# MIXR_UI.net
KiCad netlist of a schematic drawn in Altium Designer
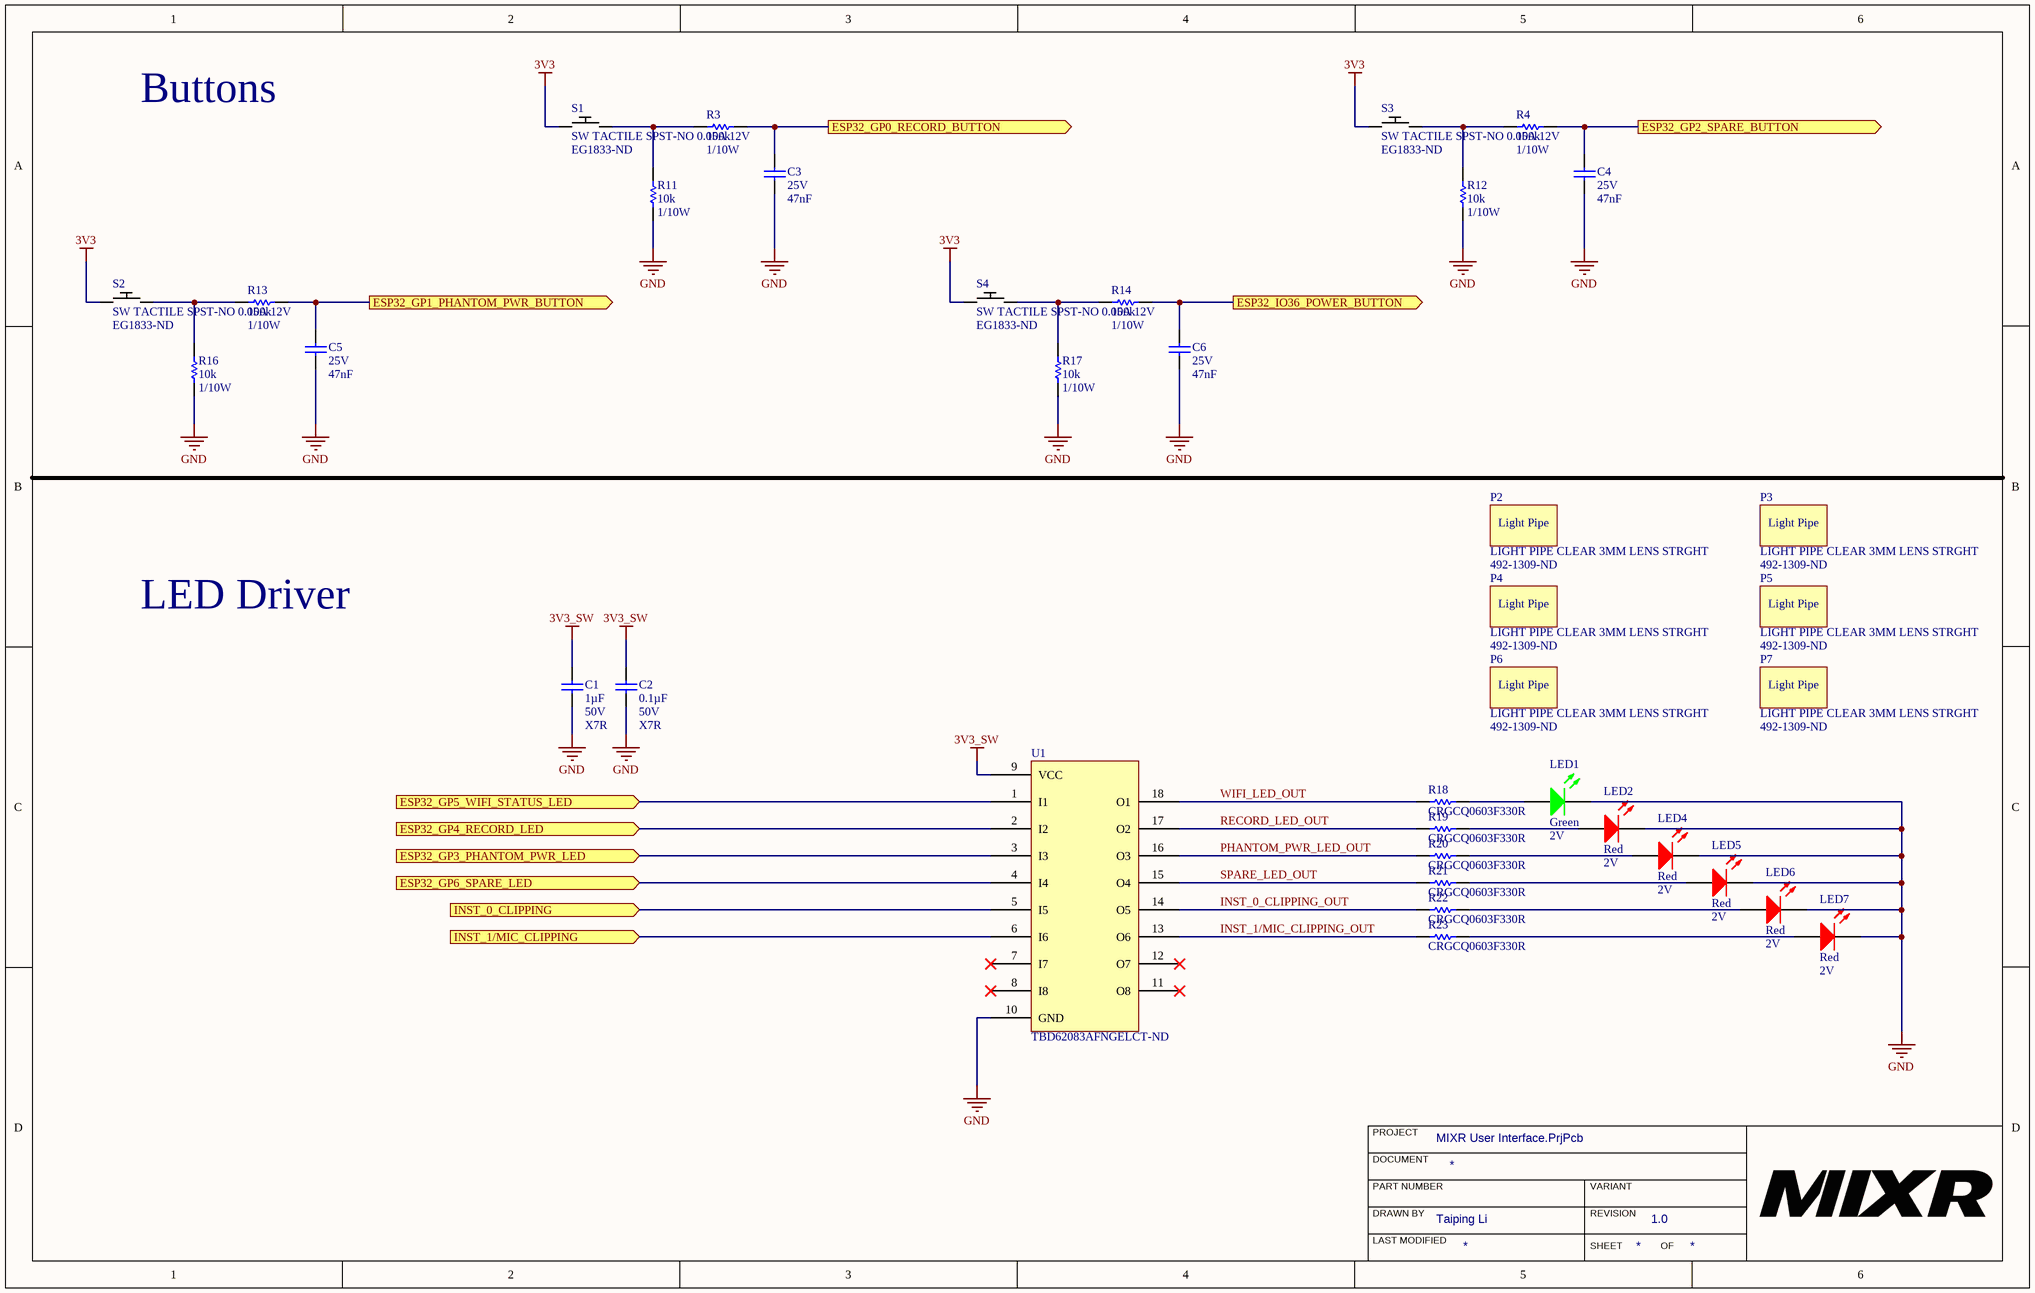
[diagram p0: MIXR UI.SchDoc]

(export (version "E")
  (design (tool "Eeschema 10.0.6"))
  (components
    (comp (ref "C1")
      (value "CAP CER 1UF 50V 10% X7R 0603")
      (footprint "CAP, 0603")
      (description "1µF ±10% 50V Ceramic Capacitor X7R 0603 (1608 Metric)")
      (fields
        (field (name "TOLERANCE") "±10%")
        (field (name "CAPACITANCE") "1µF")
        (field (name "VOLTAGE") "50V")
        (field (name "TEMPERATURE COEFFICIENT") "X7R")
      )
      (libsource (lib "Schematic Diagrams") (part "CAP CER 1UF 50V 10% X7R 0603"))
    )
    (comp (ref "C2")
      (value "CAP CER 0.1UF 50V 10% X7R 0603")
      (footprint "CAP, 0603")
      (description "0.10µF ±10% 50V Ceramic Capacitor X7R 0603 (1608 Metric)")
      (fields
        (field (name "TOLERANCE") "±10%")
        (field (name "CAPACITANCE") "0.1µF")
        (field (name "VOLTAGE") "50V")
        (field (name "TEMPERATURE COEFFICIENT") "X7R")
      )
      (libsource (lib "Schematic Diagrams") (part "CAP CER 0.1UF 50V 10% X7R 0603"))
    )
    (comp (ref "C3")
      (value "CAP CER 0.047UF 10% 25V X7R 0603")
      (footprint "CAP, 0603")
      (description "0.047µF ±10% 25V Ceramic Capacitor X7R 0603 (1608 Metric)")
      (fields
        (field (name "MANUFACTURER") "KEMET")
        (field (name "TOLERANCE") "10%")
        (field (name "VOLTAGE") "25V")
        (field (name "CAPACITANCE") "47nF")
      )
      (libsource (lib "Schematic Diagrams") (part "CAP CER 0.047UF 10% 25V X7R 0603"))
    )
    (comp (ref "C4")
      (value "CAP CER 0.047UF 10% 25V X7R 0603")
      (footprint "CAP, 0603")
      (description "0.047µF ±10% 25V Ceramic Capacitor X7R 0603 (1608 Metric)")
      (fields
        (field (name "MANUFACTURER") "KEMET")
        (field (name "TOLERANCE") "10%")
        (field (name "VOLTAGE") "25V")
        (field (name "CAPACITANCE") "47nF")
      )
      (libsource (lib "Schematic Diagrams") (part "CAP CER 0.047UF 10% 25V X7R 0603"))
    )
    (comp (ref "C5")
      (value "CAP CER 0.047UF 10% 25V X7R 0603")
      (footprint "CAP, 0603")
      (description "0.047µF ±10% 25V Ceramic Capacitor X7R 0603 (1608 Metric)")
      (fields
        (field (name "MANUFACTURER") "KEMET")
        (field (name "TOLERANCE") "10%")
        (field (name "VOLTAGE") "25V")
        (field (name "CAPACITANCE") "47nF")
      )
      (libsource (lib "Schematic Diagrams") (part "CAP CER 0.047UF 10% 25V X7R 0603"))
    )
    (comp (ref "C6")
      (value "CAP CER 0.047UF 10% 25V X7R 0603")
      (footprint "CAP, 0603")
      (description "0.047µF ±10% 25V Ceramic Capacitor X7R 0603 (1608 Metric)")
      (fields
        (field (name "MANUFACTURER") "KEMET")
        (field (name "TOLERANCE") "10%")
        (field (name "VOLTAGE") "25V")
        (field (name "CAPACITANCE") "47nF")
      )
      (libsource (lib "Schematic Diagrams") (part "CAP CER 0.047UF 10% 25V X7R 0603"))
    )
    (comp (ref "LED1")
      (value "LED GREEN CLEAR 2V 0603")
      (footprint "LED_0603")
      (description "Green 572nm LED Indication - Discrete 2V 0603 (1608 Metric)")
      (fields
        (field (name "MANUFACTURER") "Wurth Electronics Inc.")
        (field (name "MANUFACTURER PART NUMBER") "150060VS75000")
        (field (name "COLOR") "Green")
        (field (name "VOLTAGE - FORWARD (VF) (TYP)") "2V")
      )
      (libsource (lib "Schematic Diagrams") (part "LED GREEN CLEAR 2V 0603"))
    )
    (comp (ref "LED2")
      (value "LED RED CLEAR 2V 0603")
      (footprint "LED_0603")
      (description "Red 631nm LED Indication - Discrete 2V 0603 (1608 Metric)")
      (fields
        (field (name "MANUFACTURER") "Wurth Electronics Inc.")
        (field (name "MANUFACTURER PART NUMBER") "150060RS75000")
        (field (name "COLOR") "Red")
        (field (name "VOLTAGE - FORWARD (VF) (TYP)") "2V")
      )
      (libsource (lib "Schematic Diagrams") (part "LED RED CLEAR 2V 0603"))
    )
    (comp (ref "LED4")
      (value "LED RED CLEAR 2V 0603")
      (footprint "LED_0603")
      (description "Red 631nm LED Indication - Discrete 2V 0603 (1608 Metric)")
      (fields
        (field (name "MANUFACTURER") "Wurth Electronics Inc.")
        (field (name "MANUFACTURER PART NUMBER") "150060RS75000")
        (field (name "COLOR") "Red")
        (field (name "VOLTAGE - FORWARD (VF) (TYP)") "2V")
      )
      (libsource (lib "Schematic Diagrams") (part "LED RED CLEAR 2V 0603"))
    )
    (comp (ref "LED5")
      (value "LED RED CLEAR 2V 0603")
      (footprint "LED_0603")
      (description "Red 631nm LED Indication - Discrete 2V 0603 (1608 Metric)")
      (fields
        (field (name "MANUFACTURER") "Wurth Electronics Inc.")
        (field (name "MANUFACTURER PART NUMBER") "150060RS75000")
        (field (name "COLOR") "Red")
        (field (name "VOLTAGE - FORWARD (VF) (TYP)") "2V")
      )
      (libsource (lib "Schematic Diagrams") (part "LED RED CLEAR 2V 0603"))
    )
    (comp (ref "LED6")
      (value "LED RED CLEAR 2V 0603")
      (footprint "LED_0603")
      (description "Red 631nm LED Indication - Discrete 2V 0603 (1608 Metric)")
      (fields
        (field (name "MANUFACTURER") "Wurth Electronics Inc.")
        (field (name "MANUFACTURER PART NUMBER") "150060RS75000")
        (field (name "COLOR") "Red")
        (field (name "VOLTAGE - FORWARD (VF) (TYP)") "2V")
      )
      (libsource (lib "Schematic Diagrams") (part "LED RED CLEAR 2V 0603"))
    )
    (comp (ref "LED7")
      (value "LED RED CLEAR 2V 0603")
      (footprint "LED_0603")
      (description "Red 631nm LED Indication - Discrete 2V 0603 (1608 Metric)")
      (fields
        (field (name "MANUFACTURER") "Wurth Electronics Inc.")
        (field (name "MANUFACTURER PART NUMBER") "150060RS75000")
        (field (name "COLOR") "Red")
        (field (name "VOLTAGE - FORWARD (VF) (TYP)") "2V")
      )
      (libsource (lib "Schematic Diagrams") (part "LED RED CLEAR 2V 0603"))
    )
    (comp (ref "P2")
      (value "LIGHT PIPE CLEAR 3MM LENS STRGHT")
      (footprint "LIGHT PIPE CLEAR 3MM LENS STRGHT")
      (description "Light Pipe Single Clear Rigid Round with Flat Top, 3mm Panel Mount, Press Fit")
      (fields
        (field (name "MANUFACTURER") "Bivar")
        (field (name "MANUFACTURER PART NUMBER") "VLP-350-F")
        (field (name "SUPPLIER PART NUMBER 1") "492-1309-ND")
      )
      (libsource (lib "altium-import") (part "root_0_LIGHT PIPE CLEAR 3MM LENS STRGHT_"))
    )
    (comp (ref "P3")
      (value "LIGHT PIPE CLEAR 3MM LENS STRGHT")
      (footprint "LIGHT PIPE CLEAR 3MM LENS STRGHT")
      (description "Light Pipe Single Clear Rigid Round with Flat Top, 3mm Panel Mount, Press Fit")
      (fields
        (field (name "MANUFACTURER") "Bivar")
        (field (name "MANUFACTURER PART NUMBER") "VLP-350-F")
        (field (name "SUPPLIER PART NUMBER 1") "492-1309-ND")
      )
      (libsource (lib "altium-import") (part "root_0_LIGHT PIPE CLEAR 3MM LENS STRGHT_"))
    )
    (comp (ref "P4")
      (value "LIGHT PIPE CLEAR 3MM LENS STRGHT")
      (footprint "LIGHT PIPE CLEAR 3MM LENS STRGHT")
      (description "Light Pipe Single Clear Rigid Round with Flat Top, 3mm Panel Mount, Press Fit")
      (fields
        (field (name "MANUFACTURER") "Bivar")
        (field (name "MANUFACTURER PART NUMBER") "VLP-350-F")
        (field (name "SUPPLIER PART NUMBER 1") "492-1309-ND")
      )
      (libsource (lib "altium-import") (part "root_0_LIGHT PIPE CLEAR 3MM LENS STRGHT_"))
    )
    (comp (ref "P5")
      (value "LIGHT PIPE CLEAR 3MM LENS STRGHT")
      (footprint "LIGHT PIPE CLEAR 3MM LENS STRGHT")
      (description "Light Pipe Single Clear Rigid Round with Flat Top, 3mm Panel Mount, Press Fit")
      (fields
        (field (name "MANUFACTURER") "Bivar")
        (field (name "MANUFACTURER PART NUMBER") "VLP-350-F")
        (field (name "SUPPLIER PART NUMBER 1") "492-1309-ND")
      )
      (libsource (lib "altium-import") (part "root_0_LIGHT PIPE CLEAR 3MM LENS STRGHT_"))
    )
    (comp (ref "P6")
      (value "LIGHT PIPE CLEAR 3MM LENS STRGHT")
      (footprint "LIGHT PIPE CLEAR 3MM LENS STRGHT")
      (description "Light Pipe Single Clear Rigid Round with Flat Top, 3mm Panel Mount, Press Fit")
      (fields
        (field (name "MANUFACTURER") "Bivar")
        (field (name "MANUFACTURER PART NUMBER") "VLP-350-F")
        (field (name "SUPPLIER PART NUMBER 1") "492-1309-ND")
      )
      (libsource (lib "altium-import") (part "root_0_LIGHT PIPE CLEAR 3MM LENS STRGHT_"))
    )
    (comp (ref "P7")
      (value "LIGHT PIPE CLEAR 3MM LENS STRGHT")
      (footprint "LIGHT PIPE CLEAR 3MM LENS STRGHT")
      (description "Light Pipe Single Clear Rigid Round with Flat Top, 3mm Panel Mount, Press Fit")
      (fields
        (field (name "MANUFACTURER") "Bivar")
        (field (name "MANUFACTURER PART NUMBER") "VLP-350-F")
        (field (name "SUPPLIER PART NUMBER 1") "492-1309-ND")
      )
      (libsource (lib "altium-import") (part "root_0_LIGHT PIPE CLEAR 3MM LENS STRGHT_"))
    )
    (comp (ref "R3")
      (value "RES 100K OHM 5% 1/8W 0603")
      (footprint "RES, 0603")
      (description "RES SMD 100K OHM 5% 1/10W 0603")
      (fields
        (field (name "TOLERANCE") "±5%")
        (field (name "RESISTANCE") "100k")
        (field (name "POWER") "1/10W")
      )
      (libsource (lib "Schematic Diagrams") (part "RES 100K OHM 5% 1/8W 0603"))
    )
    (comp (ref "R4")
      (value "RES 100K OHM 5% 1/8W 0603")
      (footprint "RES, 0603")
      (description "RES SMD 100K OHM 5% 1/10W 0603")
      (fields
        (field (name "TOLERANCE") "±5%")
        (field (name "RESISTANCE") "100k")
        (field (name "POWER") "1/10W")
      )
      (libsource (lib "Schematic Diagrams") (part "RES 100K OHM 5% 1/8W 0603"))
    )
    (comp (ref "R11")
      (value "RES 10K OHM 1% 1/10W 0603")
      (footprint "RES, 0603")
      (description "RES SMD 10K OHM 1% 1/10W 0603")
      (fields
        (field (name "TOLERANCE") "±1%")
        (field (name "RESISTANCE") "10k")
        (field (name "POWER") "1/10W")
      )
      (libsource (lib "Schematic Diagrams") (part "RES 10K OHM 1% 1/10W 0603"))
    )
    (comp (ref "R12")
      (value "RES 10K OHM 1% 1/10W 0603")
      (footprint "RES, 0603")
      (description "RES SMD 10K OHM 1% 1/10W 0603")
      (fields
        (field (name "TOLERANCE") "±1%")
        (field (name "RESISTANCE") "10k")
        (field (name "POWER") "1/10W")
      )
      (libsource (lib "Schematic Diagrams") (part "RES 10K OHM 1% 1/10W 0603"))
    )
    (comp (ref "R13")
      (value "RES 100K OHM 5% 1/8W 0603")
      (footprint "RES, 0603")
      (description "RES SMD 100K OHM 5% 1/10W 0603")
      (fields
        (field (name "TOLERANCE") "±5%")
        (field (name "RESISTANCE") "100k")
        (field (name "POWER") "1/10W")
      )
      (libsource (lib "Schematic Diagrams") (part "RES 100K OHM 5% 1/8W 0603"))
    )
    (comp (ref "R14")
      (value "RES 100K OHM 5% 1/8W 0603")
      (footprint "RES, 0603")
      (description "RES SMD 100K OHM 5% 1/10W 0603")
      (fields
        (field (name "TOLERANCE") "±5%")
        (field (name "RESISTANCE") "100k")
        (field (name "POWER") "1/10W")
      )
      (libsource (lib "Schematic Diagrams") (part "RES 100K OHM 5% 1/8W 0603"))
    )
    (comp (ref "R16")
      (value "RES 10K OHM 1% 1/10W 0603")
      (footprint "RES, 0603")
      (description "RES SMD 10K OHM 1% 1/10W 0603")
      (fields
        (field (name "TOLERANCE") "±1%")
        (field (name "RESISTANCE") "10k")
        (field (name "POWER") "1/10W")
      )
      (libsource (lib "Schematic Diagrams") (part "RES 10K OHM 1% 1/10W 0603"))
    )
    (comp (ref "R17")
      (value "RES 10K OHM 1% 1/10W 0603")
      (footprint "RES, 0603")
      (description "RES SMD 10K OHM 1% 1/10W 0603")
      (fields
        (field (name "TOLERANCE") "±1%")
        (field (name "RESISTANCE") "10k")
        (field (name "POWER") "1/10W")
      )
      (libsource (lib "Schematic Diagrams") (part "RES 10K OHM 1% 1/10W 0603"))
    )
    (comp (ref "R18")
      (value "RES 330 OHM 1% 1/10W 0603")
      (footprint "RES, 0603")
      (fields
        (field (name "MANUFACTURER") "TE Connectivity")
        (field (name "MANUFACTURER PART NUMBER") "CRGCQ0603F330R")
      )
      (libsource (lib "Schematic Diagrams") (part "RES 330 OHM 1% 1/10W 0603"))
    )
    (comp (ref "R19")
      (value "RES 330 OHM 1% 1/10W 0603")
      (footprint "RES, 0603")
      (fields
        (field (name "MANUFACTURER") "TE Connectivity")
        (field (name "MANUFACTURER PART NUMBER") "CRGCQ0603F330R")
      )
      (libsource (lib "Schematic Diagrams") (part "RES 330 OHM 1% 1/10W 0603"))
    )
    (comp (ref "R20")
      (value "RES 330 OHM 1% 1/10W 0603")
      (footprint "RES, 0603")
      (fields
        (field (name "MANUFACTURER") "TE Connectivity")
        (field (name "MANUFACTURER PART NUMBER") "CRGCQ0603F330R")
      )
      (libsource (lib "Schematic Diagrams") (part "RES 330 OHM 1% 1/10W 0603"))
    )
    (comp (ref "R21")
      (value "RES 330 OHM 1% 1/10W 0603")
      (footprint "RES, 0603")
      (fields
        (field (name "MANUFACTURER") "TE Connectivity")
        (field (name "MANUFACTURER PART NUMBER") "CRGCQ0603F330R")
      )
      (libsource (lib "Schematic Diagrams") (part "RES 330 OHM 1% 1/10W 0603"))
    )
    (comp (ref "R22")
      (value "RES 330 OHM 1% 1/10W 0603")
      (footprint "RES, 0603")
      (fields
        (field (name "MANUFACTURER") "TE Connectivity")
        (field (name "MANUFACTURER PART NUMBER") "CRGCQ0603F330R")
      )
      (libsource (lib "Schematic Diagrams") (part "RES 330 OHM 1% 1/10W 0603"))
    )
    (comp (ref "R23")
      (value "RES 330 OHM 1% 1/10W 0603")
      (footprint "RES, 0603")
      (fields
        (field (name "MANUFACTURER") "TE Connectivity")
        (field (name "MANUFACTURER PART NUMBER") "CRGCQ0603F330R")
      )
      (libsource (lib "Schematic Diagrams") (part "RES 330 OHM 1% 1/10W 0603"))
    )
    (comp (ref "S1")
      (value "SW TACTILE SPST-NO 0.05A 12V")
      (footprint "SW SPST-NO 6x6mm Via Hole")
      (description "Tactile Switch SPST-NO Top Actuated Through Hole")
      (fields
        (field (name "MANUFACTURER") "E-Switch")
        (field (name "MANUFACTURER PART NUMBER") "TL1105BF160Q")
        (field (name "SUPPLIER PART NUMBER 1") "EG1833-ND")
      )
      (libsource (lib "Schematic Diagrams") (part "SW TACTILE SPST-NO 0.05A 12V"))
    )
    (comp (ref "S2")
      (value "SW TACTILE SPST-NO 0.05A 12V")
      (footprint "SW SPST-NO 6x6mm Via Hole")
      (description "Tactile Switch SPST-NO Top Actuated Through Hole")
      (fields
        (field (name "MANUFACTURER") "E-Switch")
        (field (name "MANUFACTURER PART NUMBER") "TL1105BF160Q")
        (field (name "SUPPLIER PART NUMBER 1") "EG1833-ND")
      )
      (libsource (lib "Schematic Diagrams") (part "SW TACTILE SPST-NO 0.05A 12V"))
    )
    (comp (ref "S3")
      (value "SW TACTILE SPST-NO 0.05A 12V")
      (footprint "SW SPST-NO 6x6mm Via Hole")
      (description "Tactile Switch SPST-NO Top Actuated Through Hole")
      (fields
        (field (name "MANUFACTURER") "E-Switch")
        (field (name "MANUFACTURER PART NUMBER") "TL1105BF160Q")
        (field (name "SUPPLIER PART NUMBER 1") "EG1833-ND")
      )
      (libsource (lib "Schematic Diagrams") (part "SW TACTILE SPST-NO 0.05A 12V"))
    )
    (comp (ref "S4")
      (value "SW TACTILE SPST-NO 0.05A 12V")
      (footprint "SW SPST-NO 6x6mm Via Hole")
      (description "Tactile Switch SPST-NO Top Actuated Through Hole")
      (fields
        (field (name "MANUFACTURER") "E-Switch")
        (field (name "MANUFACTURER PART NUMBER") "TL1105BF160Q")
        (field (name "SUPPLIER PART NUMBER 1") "EG1833-ND")
      )
      (libsource (lib "Schematic Diagrams") (part "SW TACTILE SPST-NO 0.05A 12V"))
    )
    (comp (ref "U1")
      (value "IC LOAD SWITCH 8CH 0.5A 18SSOP")
      (footprint "IC LOAD SWITCH 8CH 0.5A 18-SSOP")
      (description "IC LOAD SWITCH 8CHANNEL 0.5A 18SSOP")
      (fields
        (field (name "MANUFACTURER") "Toshiba")
        (field (name "MANUFACTURER PART NUMBER") "TBD62083AFNG,EL")
        (field (name "SUPPLIER PART NUMBER 1") "TBD62083AFNGELCT-ND")
      )
      (libsource (lib "Schematic Diagrams") (part "IC LOAD SWITCH 8CH 0.5A 18SSOP"))
    )
  )
  (nets
    (net (code "1") (name "/ESP32_GP0_RECORD_BUTTON") (class "Default")
      (node (ref "C3") (pin "1") (pinfunction "1_1") (pintype "passive"))
      (node (ref "R3") (pin "2") (pinfunction "2_2") (pintype "passive"))
    )
    (net (code "2") (name "/ESP32_GP1_PHANTOM_PWR_BUTTON") (class "Default")
      (node (ref "C5") (pin "1") (pinfunction "1_1") (pintype "passive"))
      (node (ref "R13") (pin "2") (pinfunction "2_2") (pintype "passive"))
    )
    (net (code "3") (name "/ESP32_GP2_SPARE_BUTTON") (class "Default")
      (node (ref "C4") (pin "1") (pinfunction "1_1") (pintype "passive"))
      (node (ref "R4") (pin "2") (pinfunction "2_2") (pintype "passive"))
    )
    (net (code "4") (name "/ESP32_GP3_PHANTOM_PWR_LED") (class "Default")
      (node (ref "U1") (pin "3") (pinfunction "I3_3") (pintype "passive"))
    )
    (net (code "5") (name "/ESP32_GP4_RECORD_LED") (class "Default")
      (node (ref "U1") (pin "2") (pinfunction "I2_2") (pintype "passive"))
    )
    (net (code "6") (name "/ESP32_GP5_WIFI_STATUS_LED") (class "Default")
      (node (ref "U1") (pin "1") (pinfunction "I1_1") (pintype "passive"))
    )
    (net (code "7") (name "/ESP32_GP6_SPARE_LED") (class "Default")
      (node (ref "U1") (pin "4") (pinfunction "I4_4") (pintype "passive"))
    )
    (net (code "8") (name "/ESP32_IO36_POWER_BUTTON") (class "Default")
      (node (ref "C6") (pin "1") (pinfunction "1_1") (pintype "passive"))
      (node (ref "R14") (pin "2") (pinfunction "2_2") (pintype "passive"))
    )
    (net (code "9") (name "/INST_0_CLIPPING") (class "Default")
      (node (ref "U1") (pin "5") (pinfunction "I5_5") (pintype "passive"))
    )
    (net (code "10") (name "/INST_0_CLIPPING_OUT") (class "Default")
      (node (ref "R22") (pin "1") (pinfunction "1_1") (pintype "passive"))
      (node (ref "U1") (pin "14") (pinfunction "O5_14") (pintype "passive"))
    )
    (net (code "11") (name "/INST_1{slash}MIC_CLIPPING") (class "Default")
      (node (ref "U1") (pin "6") (pinfunction "I6_6") (pintype "passive"))
    )
    (net (code "12") (name "/INST_1{slash}MIC_CLIPPING_OUT") (class "Default")
      (node (ref "R23") (pin "1") (pinfunction "1_1") (pintype "passive"))
      (node (ref "U1") (pin "13") (pinfunction "O6_13") (pintype "passive"))
    )
    (net (code "13") (name "/PHANTOM_PWR_LED_OUT") (class "Default")
      (node (ref "R20") (pin "1") (pinfunction "1_1") (pintype "passive"))
      (node (ref "U1") (pin "16") (pinfunction "O3_16") (pintype "passive"))
    )
    (net (code "14") (name "/RECORD_LED_OUT") (class "Default")
      (node (ref "R19") (pin "1") (pinfunction "1_1") (pintype "passive"))
      (node (ref "U1") (pin "17") (pinfunction "O2_17") (pintype "passive"))
    )
    (net (code "15") (name "/SPARE_LED_OUT") (class "Default")
      (node (ref "R21") (pin "1") (pinfunction "1_1") (pintype "passive"))
      (node (ref "U1") (pin "15") (pinfunction "O4_15") (pintype "passive"))
    )
    (net (code "16") (name "/WIFI_LED_OUT") (class "Default")
      (node (ref "R18") (pin "1") (pinfunction "1_1") (pintype "passive"))
      (node (ref "U1") (pin "18") (pinfunction "O1_18") (pintype "passive"))
    )
    (net (code "17") (name "3V3") (class "Default")
      (node (ref "S1") (pin "1") (pinfunction "1_1") (pintype "passive"))
      (node (ref "S2") (pin "1") (pinfunction "1_1") (pintype "passive"))
      (node (ref "S3") (pin "1") (pinfunction "1_1") (pintype "passive"))
      (node (ref "S4") (pin "1") (pinfunction "1_1") (pintype "passive"))
    )
    (net (code "18") (name "3V3_SW") (class "Default")
      (node (ref "C1") (pin "1") (pinfunction "1_1") (pintype "passive"))
      (node (ref "C2") (pin "1") (pinfunction "1_1") (pintype "passive"))
      (node (ref "U1") (pin "9") (pinfunction "VCC_9") (pintype "passive"))
    )
    (net (code "19") (name "GND") (class "Default")
      (node (ref "C1") (pin "2") (pinfunction "2_2") (pintype "passive"))
      (node (ref "C2") (pin "2") (pinfunction "2_2") (pintype "passive"))
      (node (ref "C3") (pin "2") (pinfunction "2_2") (pintype "passive"))
      (node (ref "C4") (pin "2") (pinfunction "2_2") (pintype "passive"))
      (node (ref "C5") (pin "2") (pinfunction "2_2") (pintype "passive"))
      (node (ref "C6") (pin "2") (pinfunction "2_2") (pintype "passive"))
      (node (ref "LED1") (pin "2") (pinfunction "K_2") (pintype "passive"))
      (node (ref "LED2") (pin "2") (pinfunction "K_2") (pintype "passive"))
      (node (ref "LED4") (pin "2") (pinfunction "K_2") (pintype "passive"))
      (node (ref "LED5") (pin "2") (pinfunction "K_2") (pintype "passive"))
      (node (ref "LED6") (pin "2") (pinfunction "K_2") (pintype "passive"))
      (node (ref "LED7") (pin "2") (pinfunction "K_2") (pintype "passive"))
      (node (ref "R11") (pin "1") (pinfunction "1_1") (pintype "passive"))
      (node (ref "R12") (pin "1") (pinfunction "1_1") (pintype "passive"))
      (node (ref "R16") (pin "1") (pinfunction "1_1") (pintype "passive"))
      (node (ref "R17") (pin "1") (pinfunction "1_1") (pintype "passive"))
      (node (ref "U1") (pin "10") (pinfunction "GND_10") (pintype "passive"))
    )
    (net (code "20") (name "Net-(LED1-A)") (class "Default")
      (node (ref "LED1") (pin "1") (pinfunction "A_1") (pintype "passive"))
      (node (ref "R18") (pin "2") (pinfunction "2_2") (pintype "passive"))
    )
    (net (code "21") (name "Net-(LED2-A)") (class "Default")
      (node (ref "LED2") (pin "1") (pinfunction "A_1") (pintype "passive"))
      (node (ref "R19") (pin "2") (pinfunction "2_2") (pintype "passive"))
    )
    (net (code "22") (name "Net-(LED4-A)") (class "Default")
      (node (ref "LED4") (pin "1") (pinfunction "A_1") (pintype "passive"))
      (node (ref "R20") (pin "2") (pinfunction "2_2") (pintype "passive"))
    )
    (net (code "23") (name "Net-(LED5-A)") (class "Default")
      (node (ref "LED5") (pin "1") (pinfunction "A_1") (pintype "passive"))
      (node (ref "R21") (pin "2") (pinfunction "2_2") (pintype "passive"))
    )
    (net (code "24") (name "Net-(LED6-A)") (class "Default")
      (node (ref "LED6") (pin "1") (pinfunction "A_1") (pintype "passive"))
      (node (ref "R22") (pin "2") (pinfunction "2_2") (pintype "passive"))
    )
    (net (code "25") (name "Net-(LED7-A)") (class "Default")
      (node (ref "LED7") (pin "1") (pinfunction "A_1") (pintype "passive"))
      (node (ref "R23") (pin "2") (pinfunction "2_2") (pintype "passive"))
    )
    (net (code "26") (name "Net-(R11-Pad2)") (class "Default")
      (node (ref "R11") (pin "2") (pinfunction "2_2") (pintype "passive"))
      (node (ref "R3") (pin "1") (pinfunction "1_1") (pintype "passive"))
      (node (ref "S1") (pin "2") (pinfunction "2_2") (pintype "passive"))
    )
    (net (code "27") (name "Net-(R12-Pad2)") (class "Default")
      (node (ref "R12") (pin "2") (pinfunction "2_2") (pintype "passive"))
      (node (ref "R4") (pin "1") (pinfunction "1_1") (pintype "passive"))
      (node (ref "S3") (pin "2") (pinfunction "2_2") (pintype "passive"))
    )
    (net (code "28") (name "Net-(R13-Pad1)") (class "Default")
      (node (ref "R13") (pin "1") (pinfunction "1_1") (pintype "passive"))
      (node (ref "R16") (pin "2") (pinfunction "2_2") (pintype "passive"))
      (node (ref "S2") (pin "2") (pinfunction "2_2") (pintype "passive"))
    )
    (net (code "29") (name "Net-(R14-Pad1)") (class "Default")
      (node (ref "R14") (pin "1") (pinfunction "1_1") (pintype "passive"))
      (node (ref "R17") (pin "2") (pinfunction "2_2") (pintype "passive"))
      (node (ref "S4") (pin "2") (pinfunction "2_2") (pintype "passive"))
    )
    (net (code "30") (name "unconnected-(U1-I7-Pad7)") (class "Default")
      (node (ref "U1") (pin "7") (pinfunction "I7_7") (pintype "passive+no_connect"))
    )
    (net (code "31") (name "unconnected-(U1-I8-Pad8)") (class "Default")
      (node (ref "U1") (pin "8") (pinfunction "I8_8") (pintype "passive+no_connect"))
    )
    (net (code "32") (name "unconnected-(U1-O7-Pad12)") (class "Default")
      (node (ref "U1") (pin "12") (pinfunction "O7_12") (pintype "passive+no_connect"))
    )
    (net (code "33") (name "unconnected-(U1-O8-Pad11)") (class "Default")
      (node (ref "U1") (pin "11") (pinfunction "O8_11") (pintype "passive+no_connect"))
    )
  )
)
